# gps-breakout-mk-1_2.net
KiCad netlist of a schematic drawn in EAGLE
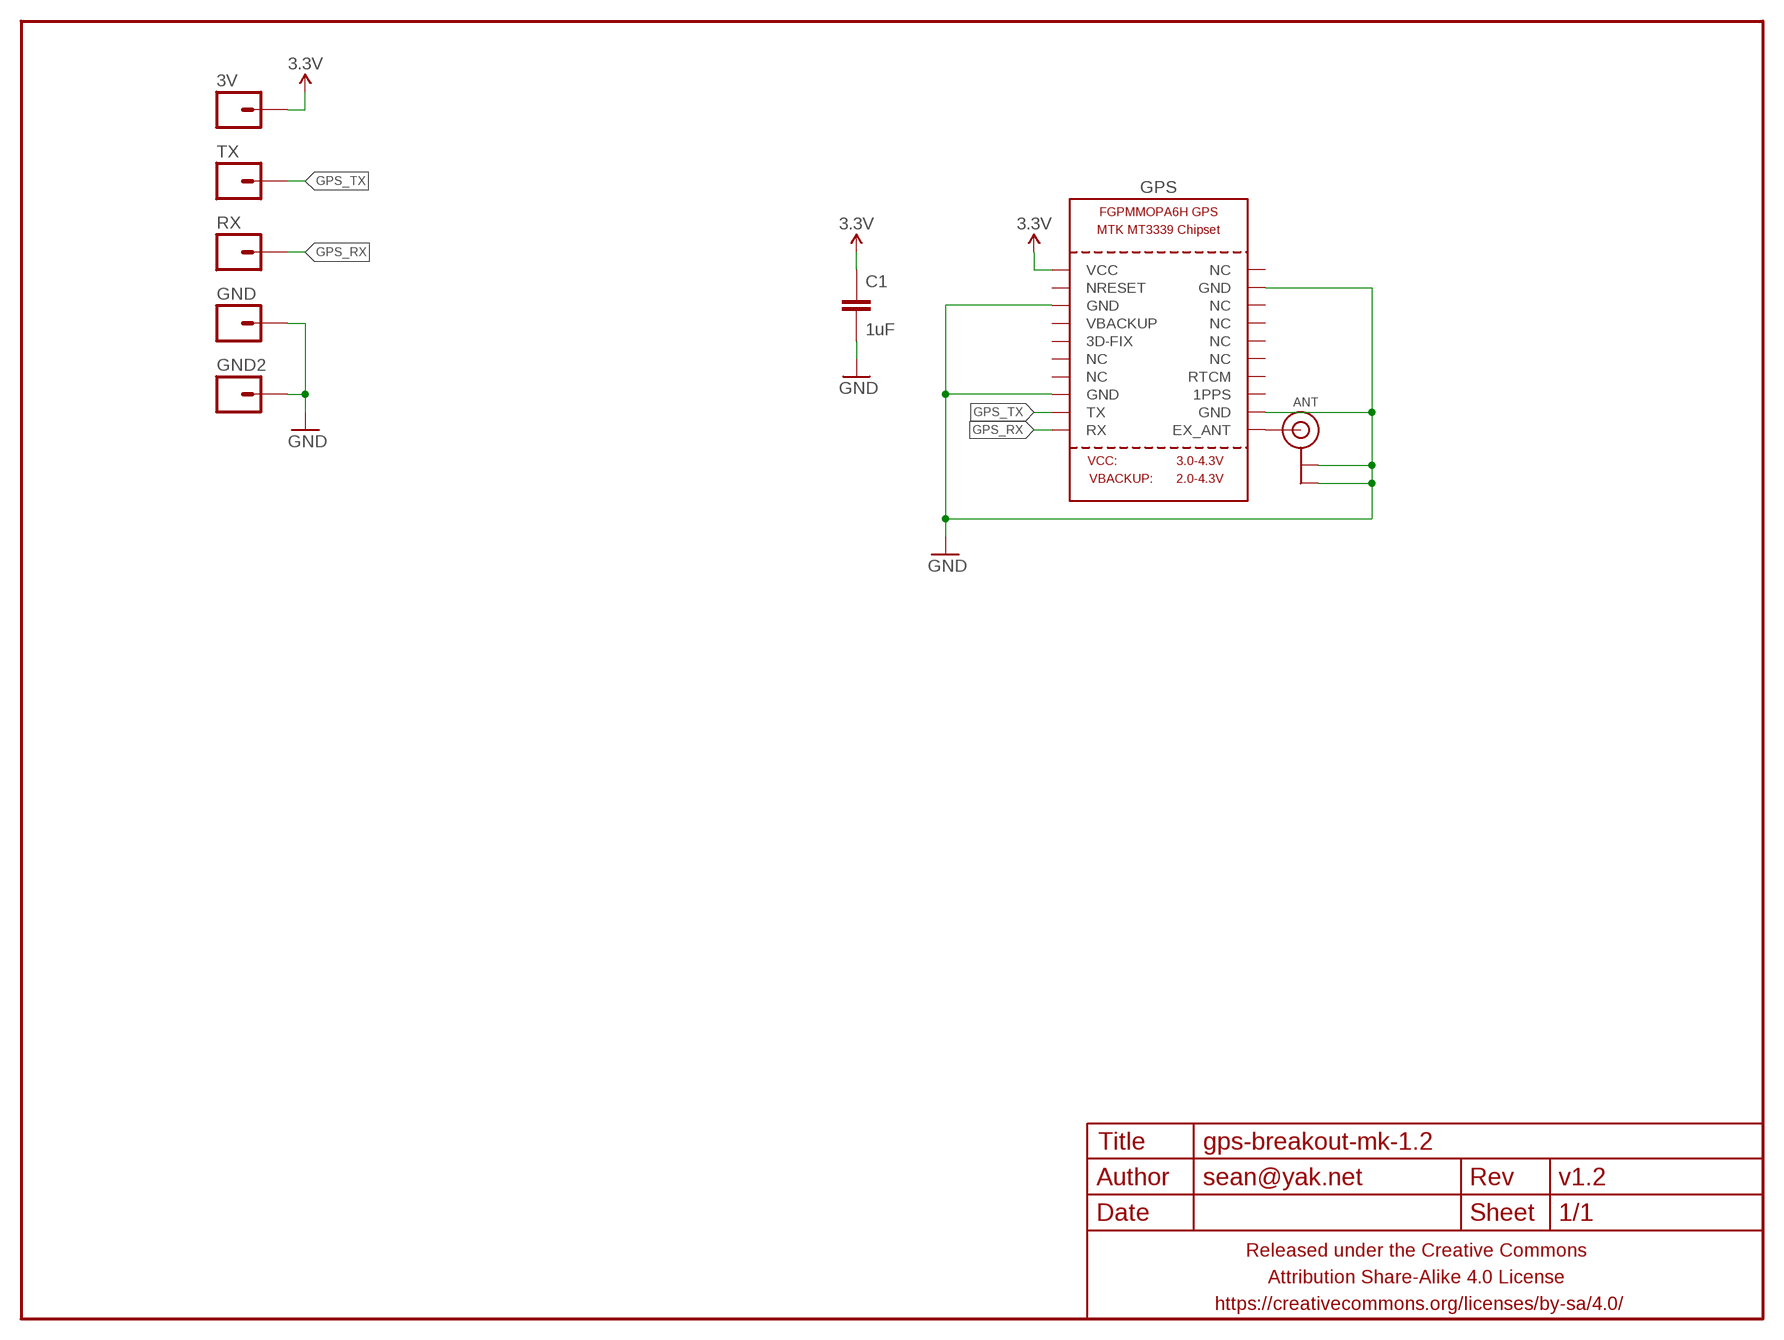
[diagram p0: schematic, sheet 1]

(export (version "E")
  (design (tool "Eeschema 10.0.6"))
  (components
    (comp (ref "3V")
      (value "M01PTH-1MM")
      (footprint "eagle-import:1X01-1MM-NS")
      (libsource (lib "eagle-import") (part "M01PTH-1MM"))
    )
    (comp (ref "ANT")
      (value "ANTENNA_U.FL")
      (footprint "eagle-import:U.FL")
      (libsource (lib "eagle-import") (part "ANTENNA_U.FL"))
    )
    (comp (ref "C1")
      (value "1uF")
      (footprint "eagle-import:C0603-TIGHTER")
      (libsource (lib "eagle-import") (part "CAPACITOR-CERAMICC0603-TIGHTER"))
    )
    (comp (ref "FRAME1")
      (value "FRAME-LETTERNO_PACKAGE")
      (footprint "eagle-import:DUMMY")
      (fields (field (name "DESIGNER") "sean@yak.net") (field (name "VERSION") "v1.2"))
      (libsource (lib "eagle-import") (part "FRAME-LETTERNO_PACKAGE"))
    )
    (comp (ref "GND")
      (value "M01PTH-1MM")
      (footprint "eagle-import:1X01-1MM-NS")
      (libsource (lib "eagle-import") (part "M01PTH-1MM"))
    )
    (comp (ref "GND2")
      (value "M01PTH-1MM")
      (footprint "eagle-import:1X01-1MM-NS")
      (libsource (lib "eagle-import") (part "M01PTH-1MM"))
    )
    (comp (ref "GPS")
      (value "GPS_FGPMMOPA6H")
      (footprint "eagle-import:FGPMMOPA6H")
      (libsource (lib "eagle-import") (part "GPS_FGPMMOPA6H"))
    )
    (comp (ref "RX")
      (value "M01PTH-1MM")
      (footprint "eagle-import:1X01-1MM-NS")
      (libsource (lib "eagle-import") (part "M01PTH-1MM"))
    )
    (comp (ref "TX")
      (value "M01PTH-1MM")
      (footprint "eagle-import:1X01-1MM-NS")
      (libsource (lib "eagle-import") (part "M01PTH-1MM"))
    )
  )
  (nets
    (net (code "1") (name "3.3V") (class "Default")
      (node (ref "3V") (pin "1") (pinfunction "1_1") (pintype "passive"))
      (node (ref "C1") (pin "1") (pinfunction "1_1") (pintype "passive"))
      (node (ref "GPS") (pin "P$1") (pinfunction "VCC_P$1") (pintype "bidirectional"))
    )
    (net (code "2") (name "GND") (class "Default")
      (node (ref "ANT") (pin "1") (pinfunction "GND_1") (pintype "passive"))
      (node (ref "ANT") (pin "2") (pinfunction "GND_2") (pintype "passive"))
      (node (ref "C1") (pin "2") (pinfunction "2_2") (pintype "passive"))
      (node (ref "GND") (pin "1") (pinfunction "1_1") (pintype "passive"))
      (node (ref "GND2") (pin "1") (pinfunction "1_1") (pintype "passive"))
      (node (ref "GPS") (pin "P$12") (pinfunction "GND_P$12") (pintype "bidirectional"))
      (node (ref "GPS") (pin "P$19") (pinfunction "GND_P$19") (pintype "bidirectional"))
      (node (ref "GPS") (pin "P$3") (pinfunction "GND_P$3") (pintype "bidirectional"))
      (node (ref "GPS") (pin "P$8") (pinfunction "GND_P$8") (pintype "bidirectional"))
    )
    (net (code "3") (name "GPS_RX") (class "Default")
      (node (ref "GPS") (pin "P$10") (pinfunction "RX_P$10") (pintype "bidirectional"))
      (node (ref "RX") (pin "1") (pinfunction "1_1") (pintype "passive"))
    )
    (net (code "4") (name "GPS_TX") (class "Default")
      (node (ref "GPS") (pin "P$9") (pinfunction "TX_P$9") (pintype "bidirectional"))
      (node (ref "TX") (pin "1") (pinfunction "1_1") (pintype "passive"))
    )
    (net (code "5") (name "Net-(ANT-SIGNAL)") (class "Default")
      (node (ref "ANT") (pin "3") (pinfunction "SIGNAL_3") (pintype "passive"))
      (node (ref "GPS") (pin "P$11") (pinfunction "EX_ANT_P$11") (pintype "bidirectional"))
    )
    (net (code "6") (name "unconnected-(GPS-1PPS-PadP$13)") (class "Default")
      (node (ref "GPS") (pin "P$13") (pinfunction "1PPS_P$13") (pintype "bidirectional"))
    )
    (net (code "7") (name "unconnected-(GPS-3D-FIX-PadP$5)") (class "Default")
      (node (ref "GPS") (pin "P$5") (pinfunction "3D-FIX_P$5") (pintype "bidirectional"))
    )
    (net (code "8") (name "unconnected-(GPS-NC-PadP$6)") (class "Default")
      (node (ref "GPS") (pin "P$6") (pinfunction "NC_P$6") (pintype "bidirectional"))
    )
    (net (code "9") (name "unconnected-(GPS-NC-PadP$7)") (class "Default")
      (node (ref "GPS") (pin "P$7") (pinfunction "NC_P$7") (pintype "bidirectional"))
    )
    (net (code "10") (name "unconnected-(GPS-NC-PadP$15)") (class "Default")
      (node (ref "GPS") (pin "P$15") (pinfunction "NC_P$15") (pintype "bidirectional"))
    )
    (net (code "11") (name "unconnected-(GPS-NC-PadP$16)") (class "Default")
      (node (ref "GPS") (pin "P$16") (pinfunction "NC_P$16") (pintype "bidirectional"))
    )
    (net (code "12") (name "unconnected-(GPS-NC-PadP$17)") (class "Default")
      (node (ref "GPS") (pin "P$17") (pinfunction "NC_P$17") (pintype "bidirectional"))
    )
    (net (code "13") (name "unconnected-(GPS-NC-PadP$18)") (class "Default")
      (node (ref "GPS") (pin "P$18") (pinfunction "NC_P$18") (pintype "bidirectional"))
    )
    (net (code "14") (name "unconnected-(GPS-NC-PadP$20)") (class "Default")
      (node (ref "GPS") (pin "P$20") (pinfunction "NC_P$20") (pintype "bidirectional"))
    )
    (net (code "15") (name "unconnected-(GPS-NRESET-PadP$2)") (class "Default")
      (node (ref "GPS") (pin "P$2") (pinfunction "NRESET_P$2") (pintype "bidirectional"))
    )
    (net (code "16") (name "unconnected-(GPS-RTCM-PadP$14)") (class "Default")
      (node (ref "GPS") (pin "P$14") (pinfunction "RTCM_P$14") (pintype "bidirectional"))
    )
    (net (code "17") (name "unconnected-(GPS-VBACKUP-PadP$4)") (class "Default")
      (node (ref "GPS") (pin "P$4") (pinfunction "VBACKUP_P$4") (pintype "bidirectional"))
    )
  )
)
